# 05_RS485.net
KiCad netlist of a schematic drawn in Altium Designer
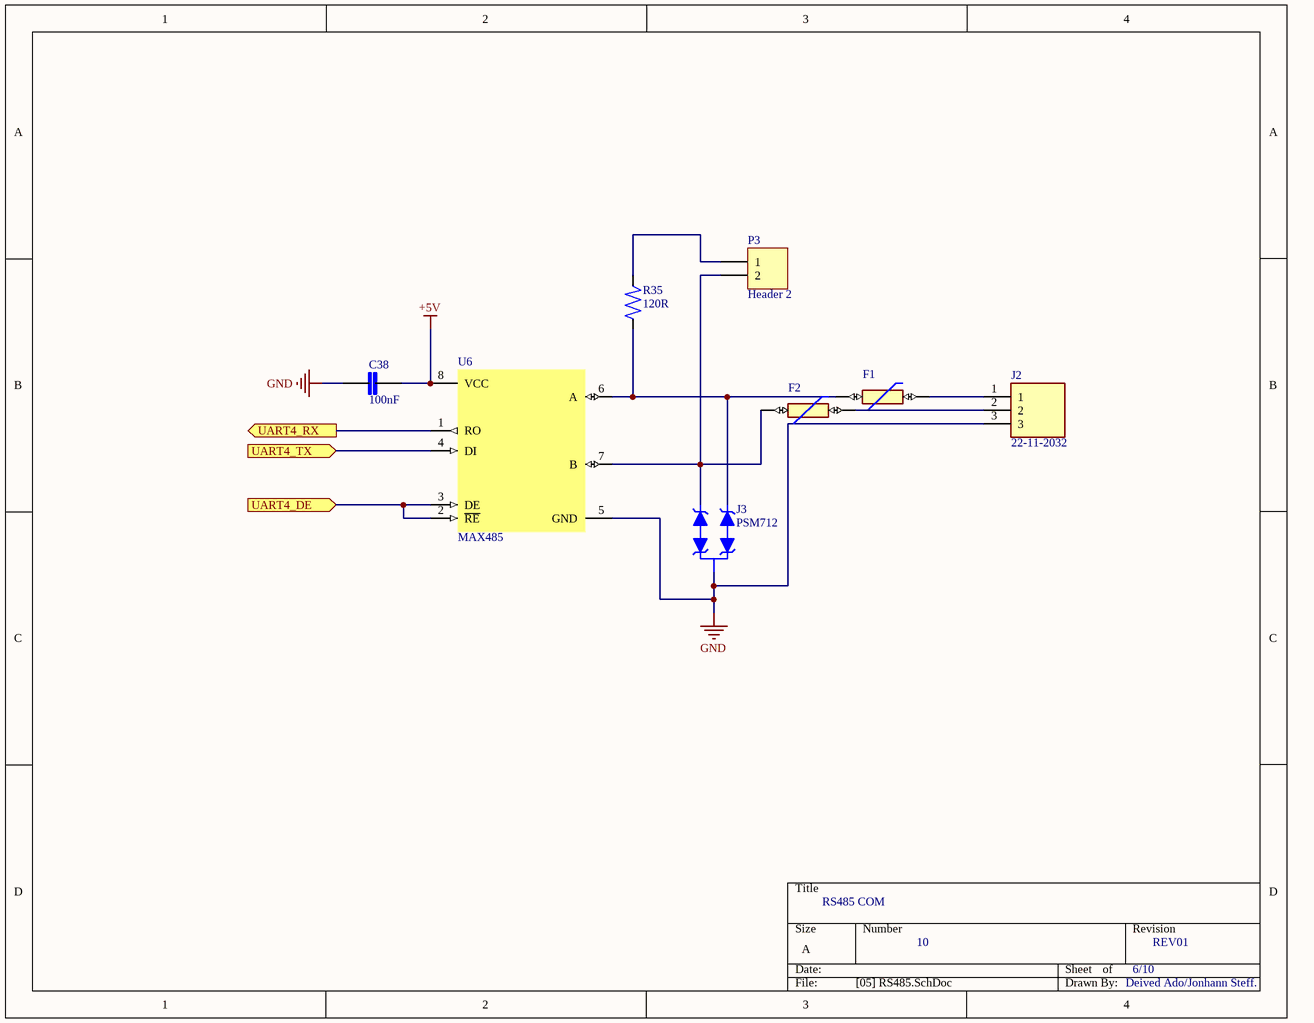
[diagram p0: [05] RS485.SchDoc]

(export (version "E")
  (design (tool "Eeschema 10.0.6"))
  (components
    (comp (ref "C38")
      (value "100nF")
      (footprint "CAP_0603")
      (description "Generic capacitor symbol")
      (libsource (lib "Integrated_Library_IST") (part "C_Small"))
    )
    (comp (ref "F1")
      (value "1206L050/15")
      (footprint "RES_1206")
      (description "Polymeric PTC Resettable Fuse 15V 500mA Ih Surface Mount 1206 (3216 Metric), Concave")
      (fields (field (name "MF") "Littelfuse"))
      (libsource (lib "Integrated_Library_IST") (part "1206L050/15"))
    )
    (comp (ref "F2")
      (value "1206L050/15")
      (footprint "res_1206")
      (description "Polymeric PTC Resettable Fuse 15V 500mA Ih Surface Mount 1206 (3216 Metric), Concave")
      (fields (field (name "MF") "Littelfuse"))
      (libsource (lib "Integrated_Library_IST") (part "1206L050/15"))
    )
    (comp (ref "J2")
      (value "22-11-2032")
      (footprint "HDRV3W87P0X254_1X3_747X635X1105P")
      (description "Molex KK 254 6373, 2.54mm Pitch, 3 Way, 1 Row, Straight PCB Header, Through Hole")
      (fields (field (name "MANUFACTURER") "Molex"))
      (libsource (lib "Integrated_Library_IST") (part "KK - HDR 3P"))
    )
    (comp (ref "J3")
      (value "PSM712")
      (footprint "sot-23-3")
      (description "ESD Suppressor Diode TVS Bi-Dir 12V/7V 3-Pin SOT-23")
      (fields (field (name "MF") "Texas Instruments"))
      (libsource (lib "Schlib7") (part "PSM712"))
    )
    (comp (ref "P3")
      (value "Header 2")
      (footprint "HDR1X2")
      (description "Header, 2-Pin")
      (fields (field (name "PUBLISHER") "Altium Limited"))
      (libsource (lib "Miscellaneous Connectors") (part "Header 2"))
    )
    (comp (ref "R35")
      (value "120R")
      (footprint "RES_0603")
      (description "Generic Resistor symbol")
      (libsource (lib "Integrated_Library_IST") (part "R_Small"))
    )
    (comp (ref "U6")
      (value "MAX485")
      (footprint "SOIC-8")
      (description "Transceiver Half RS422, RS485 8-SOIC")
      (fields
        (field (name "MFR. PART #") "MAX485ESA+")
        (field (name "MANUFACTURER") "Analog Devices / Maxim Integrated")
      )
      (libsource (lib "Schlib7") (part "MAX485"))
    )
  )
  (nets
    (net (code "1") (name "+5V") (class "Default")
      (node (ref "C38") (pin "2") (pinfunction "2_2") (pintype "passive"))
      (node (ref "U6") (pin "8") (pinfunction "VCC_8") (pintype "power_in"))
    )
    (net (code "2") (name "/UART4_DE") (class "Default")
      (node (ref "U6") (pin "2") (pinfunction "~{RE}_2") (pintype "input"))
      (node (ref "U6") (pin "3") (pinfunction "DE_3") (pintype "input"))
    )
    (net (code "3") (name "/UART4_RX") (class "Default")
      (node (ref "U6") (pin "1") (pinfunction "RO_1") (pintype "output"))
    )
    (net (code "4") (name "/UART4_TX") (class "Default")
      (node (ref "U6") (pin "4") (pinfunction "DI_4") (pintype "input"))
    )
    (net (code "5") (name "GND") (class "Default")
      (node (ref "C38") (pin "1") (pinfunction "1_1") (pintype "passive"))
      (node (ref "J2") (pin "3") (pinfunction "3_3") (pintype "passive"))
      (node (ref "J3") (pin "3") (pinfunction "C_3") (pintype "passive"))
      (node (ref "U6") (pin "5") (pinfunction "GND_5") (pintype "power_in"))
    )
    (net (code "6") (name "Net-(F1-Pad2)") (class "Default")
      (node (ref "F1") (pin "2") (pinfunction "2_2") (pintype "bidirectional"))
      (node (ref "J2") (pin "1") (pinfunction "1_1") (pintype "passive"))
    )
    (net (code "7") (name "Net-(F2-Pad2)") (class "Default")
      (node (ref "F2") (pin "2") (pinfunction "2_2") (pintype "bidirectional"))
      (node (ref "J2") (pin "2") (pinfunction "2_2") (pintype "passive"))
    )
    (net (code "8") (name "Net-(J3-A)") (class "Default")
      (node (ref "F1") (pin "1") (pinfunction "1_1") (pintype "bidirectional"))
      (node (ref "J3") (pin "1") (pinfunction "A_1") (pintype "passive"))
      (node (ref "R35") (pin "1") (pinfunction "1_1") (pintype "passive"))
      (node (ref "U6") (pin "6") (pinfunction "A_6") (pintype "bidirectional"))
    )
    (net (code "9") (name "Net-(J3-A1)") (class "Default")
      (node (ref "F2") (pin "1") (pinfunction "1_1") (pintype "bidirectional"))
      (node (ref "J3") (pin "2") (pinfunction "A1_2") (pintype "passive"))
      (node (ref "P3") (pin "2") (pinfunction "2_2") (pintype "passive"))
      (node (ref "U6") (pin "7") (pinfunction "B_7") (pintype "bidirectional"))
    )
    (net (code "10") (name "Net-(P3-Pad1)") (class "Default")
      (node (ref "P3") (pin "1") (pinfunction "1_1") (pintype "passive"))
      (node (ref "R35") (pin "2") (pinfunction "2_2") (pintype "passive"))
    )
  )
)
